# ADS_1.net
KiCad netlist of a schematic drawn in Altium Designer
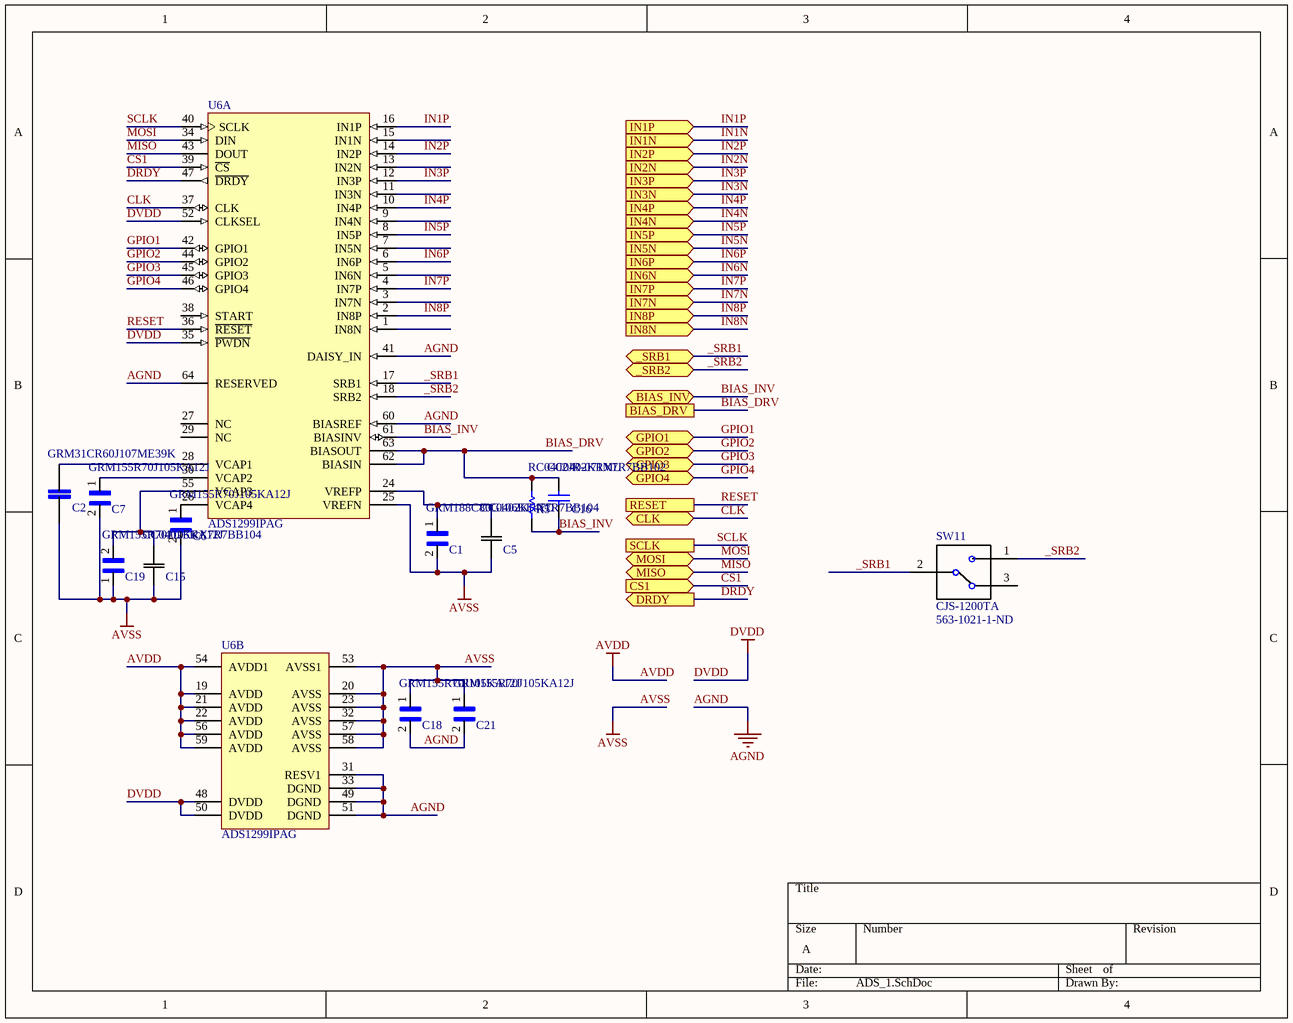
[diagram p0: ADS_1.SchDoc]

(export (version "E")
  (design (tool "Eeschema 10.0.6"))
  (components
    (comp (ref "C1")
      (value "GRM188C80G106KE47D")
      (footprint "*CAPC1608X90N")
      (description "CAP CER 10UF 4V X6S 0603")
      (fields (field (name "TOLERANCE") "10%"))
      (libsource (lib "EE_smallOB_BW_v1.0") (part "GRM188C80G106KE47D"))
    )
    (comp (ref "C2")
      (value "GRM31CR60J107ME39K")
      (footprint "*CAPC3216X190")
      (description "MURATA - GRM31CR60J107ME39K - COND, 100µF, 6.3V, 20%, X5R, 1206")
      (fields (field (name "TOLERANCE") "20%") (field (name "VOLTAGE") "6.3V"))
      (libsource (lib "EE_smallOB_BW_v1.0") (part "GRM31CR60J107ME39K"))
    )
    (comp (ref "C5")
      (value "CC0402KRX7R7BB104")
      (footprint "YAG_CC0402")
      (description "CAP CER 0.1UF 16V X7R 0402")
      (fields (field (name "TOLERANCE") "10%") (field (name "VOLTAGE") "16V"))
      (libsource (lib "EE_smallOB_BW_v1.0") (part "CC0402KRX7R7BB104"))
    )
    (comp (ref "C6")
      (value "GRM155R70J105KA12J")
      (footprint "*CAPC1005X55N")
      (description "CAP CER 1UF 6.3V X7R 0402")
      (fields (field (name "TOLERANCE") "10%"))
      (libsource (lib "EE_smallOB_BW_v1.0") (part "GRM155R70J105KA12J"))
    )
    (comp (ref "C7")
      (value "GRM155R70J105KA12J")
      (footprint "*CAPC1005X55N")
      (description "CAP CER 1UF 6.3V X7R 0402")
      (fields (field (name "TOLERANCE") "10%"))
      (libsource (lib "EE_smallOB_BW_v1.0") (part "GRM155R70J105KA12J"))
    )
    (comp (ref "C15")
      (value "CC0402KRX7R7BB104")
      (footprint "YAG_CC0402")
      (description "CAP CER 0.1UF 16V X7R 0402")
      (fields (field (name "TOLERANCE") "10%") (field (name "VOLTAGE") "16V"))
      (libsource (lib "EE_smallOB_BW_v1.0") (part "CC0402KRX7R7BB104"))
    )
    (comp (ref "C16")
      (value "CC0402KRX7R7BB102")
      (footprint "CAPC1005X55X23NL05T08")
      (description "CAP CER 1000PF 16V X7R 0402")
      (fields (field (name "TOLERANCE") "10%"))
      (libsource (lib "EE_smallOB_BW_v1.0") (part "CC0402KRX7R7BB102"))
    )
    (comp (ref "C18")
      (value "GRM155R70J105KA12J")
      (footprint "*CAPC1005X55N")
      (description "CAP CER 1UF 6.3V X7R 0402")
      (fields (field (name "TOLERANCE") "10%"))
      (libsource (lib "EE_smallOB_BW_v1.0") (part "GRM155R70J105KA12J"))
    )
    (comp (ref "C19")
      (value "GRM155R70J105KA12J")
      (footprint "*CAPC1005X55N")
      (description "CAP CER 1UF 6.3V X7R 0402")
      (fields (field (name "TOLERANCE") "10%"))
      (libsource (lib "EE_smallOB_BW_v1.0") (part "GRM155R70J105KA12J"))
    )
    (comp (ref "C21")
      (value "GRM155R70J105KA12J")
      (footprint "*CAPC1005X55N")
      (description "CAP CER 1UF 6.3V X7R 0402")
      (fields (field (name "TOLERANCE") "10%"))
      (libsource (lib "EE_smallOB_BW_v1.0") (part "GRM155R70J105KA12J"))
    )
    (comp (ref "R5")
      (value "RC0402JR-071ML")
      (footprint "RESC1005X40X25NL05T10")
      (description "RES SMD 1M OHM 5% 1/16W 0402")
      (fields (field (name "TOLERANCE") "5%"))
      (libsource (lib "EE_smallOB_BW_v1.0") (part "RC0402JR-071ML"))
    )
    (comp (ref "SW11")
      (value "CJS-1200TA")
      (footprint "*SW_CJS-1200TA")
      (description "SWITCH SLIDE SPDT 100MA 6V")
      (fields (field (name "SUPPLIER PART NUMBER 1") "563-1021-1-ND"))
      (libsource (lib "EE_smallOB_BW_v1.0") (part "CJS-1200TA"))
    )
    (comp (ref "U6")
      (value "ADS1299IPAG")
      (footprint "PAG0064A_N")
      (description "IC AFE 24BIT 16KSPS LN 64TQFP")
      (libsource (lib "EE_smallOB_BW_v1.0") (part "ADS1299IPAG"))
    )
  )
  (nets
    (net (code "1") (name "/BIAS_DRV") (class "Default")
      (node (ref "C16") (pin "1") (pinfunction "1_1") (pintype "passive"))
      (node (ref "R5") (pin "1") (pinfunction "1_1") (pintype "passive"))
      (node (ref "U6") (pin "62") (pinfunction "BIASIN_62") (pintype "passive"))
      (node (ref "U6") (pin "63") (pinfunction "BIASOUT_63") (pintype "passive"))
    )
    (net (code "2") (name "/BIAS_INV") (class "Default")
      (node (ref "C16") (pin "2") (pinfunction "2_2") (pintype "passive"))
      (node (ref "R5") (pin "2") (pinfunction "2_2") (pintype "passive"))
      (node (ref "U6") (pin "61") (pinfunction "BIASINV_61") (pintype "bidirectional"))
    )
    (net (code "3") (name "/CLK") (class "Default")
      (node (ref "U6") (pin "37") (pinfunction "CLK_37") (pintype "bidirectional"))
    )
    (net (code "4") (name "/CS1") (class "Default")
      (node (ref "U6") (pin "39") (pinfunction "~{CS}_39") (pintype "input"))
    )
    (net (code "5") (name "/DRDY") (class "Default")
      (node (ref "U6") (pin "47") (pinfunction "~{DRDY}_47") (pintype "output"))
    )
    (net (code "6") (name "/GPIO1") (class "Default")
      (node (ref "U6") (pin "42") (pinfunction "GPIO1_42") (pintype "bidirectional"))
    )
    (net (code "7") (name "/GPIO2") (class "Default")
      (node (ref "U6") (pin "44") (pinfunction "GPIO2_44") (pintype "bidirectional"))
    )
    (net (code "8") (name "/GPIO3") (class "Default")
      (node (ref "U6") (pin "45") (pinfunction "GPIO3_45") (pintype "bidirectional"))
    )
    (net (code "9") (name "/GPIO4") (class "Default")
      (node (ref "U6") (pin "46") (pinfunction "GPIO4_46") (pintype "bidirectional"))
    )
    (net (code "11") (name "/IN1P") (class "Default")
      (node (ref "U6") (pin "16") (pinfunction "IN1P_16") (pintype "input"))
    )
    (net (code "13") (name "/IN2P") (class "Default")
      (node (ref "U6") (pin "14") (pinfunction "IN2P_14") (pintype "input"))
    )
    (net (code "15") (name "/IN3P") (class "Default")
      (node (ref "U6") (pin "12") (pinfunction "IN3P_12") (pintype "input"))
    )
    (net (code "17") (name "/IN4P") (class "Default")
      (node (ref "U6") (pin "10") (pinfunction "IN4P_10") (pintype "input"))
    )
    (net (code "19") (name "/IN5P") (class "Default")
      (node (ref "U6") (pin "8") (pinfunction "IN5P_8") (pintype "input"))
    )
    (net (code "21") (name "/IN6P") (class "Default")
      (node (ref "U6") (pin "6") (pinfunction "IN6P_6") (pintype "input"))
    )
    (net (code "23") (name "/IN7P") (class "Default")
      (node (ref "U6") (pin "4") (pinfunction "IN7P_4") (pintype "input"))
    )
    (net (code "25") (name "/IN8P") (class "Default")
      (node (ref "U6") (pin "2") (pinfunction "IN8P_2") (pintype "input"))
    )
    (net (code "26") (name "/MISO") (class "Default")
      (node (ref "U6") (pin "43") (pinfunction "DOUT_43") (pintype "tri_state"))
    )
    (net (code "27") (name "/MOSI") (class "Default")
      (node (ref "U6") (pin "34") (pinfunction "DIN_34") (pintype "input"))
    )
    (net (code "28") (name "/RESET") (class "Default")
      (node (ref "U6") (pin "36") (pinfunction "~{RESET}_36") (pintype "input"))
    )
    (net (code "29") (name "/SCLK") (class "Default")
      (node (ref "U6") (pin "40") (pinfunction "SCLK_40") (pintype "input"))
    )
    (net (code "30") (name "/_SRB1") (class "Default")
      (node (ref "SW11") (pin "2") (pinfunction "2_2") (pintype "passive"))
      (node (ref "U6") (pin "17") (pinfunction "SRB1_17") (pintype "input"))
    )
    (net (code "31") (name "/_SRB2") (class "Default")
      (node (ref "SW11") (pin "1") (pinfunction "1_1") (pintype "passive"))
      (node (ref "U6") (pin "18") (pinfunction "SRB2_18") (pintype "input"))
    )
    (net (code "32") (name "AGND") (class "Default")
      (node (ref "C18") (pin "2") (pinfunction "2_2") (pintype "passive"))
      (node (ref "C21") (pin "2") (pinfunction "2_2") (pintype "passive"))
      (node (ref "U6") (pin "31") (pinfunction "RESV1_31") (pintype "power_in"))
      (node (ref "U6") (pin "33") (pinfunction "DGND_33") (pintype "power_in"))
      (node (ref "U6") (pin "41") (pinfunction "DAISY_IN_41") (pintype "input"))
      (node (ref "U6") (pin "49") (pinfunction "DGND_49") (pintype "power_in"))
      (node (ref "U6") (pin "51") (pinfunction "DGND_51") (pintype "power_in"))
      (node (ref "U6") (pin "60") (pinfunction "BIASREF_60") (pintype "input"))
      (node (ref "U6") (pin "64") (pinfunction "RESERVED_64") (pintype "passive"))
    )
    (net (code "33") (name "AVDD") (class "Default")
      (node (ref "U6") (pin "19") (pinfunction "AVDD_19") (pintype "power_in"))
      (node (ref "U6") (pin "21") (pinfunction "AVDD_21") (pintype "power_in"))
      (node (ref "U6") (pin "22") (pinfunction "AVDD_22") (pintype "power_in"))
      (node (ref "U6") (pin "54") (pinfunction "AVDD1_54") (pintype "power_in"))
      (node (ref "U6") (pin "56") (pinfunction "AVDD_56") (pintype "power_in"))
      (node (ref "U6") (pin "59") (pinfunction "AVDD_59") (pintype "power_in"))
    )
    (net (code "34") (name "AVSS") (class "Default")
      (node (ref "C1") (pin "2") (pinfunction "2_2") (pintype "passive"))
      (node (ref "C15") (pin "1") (pinfunction "1_1") (pintype "passive"))
      (node (ref "C18") (pin "1") (pinfunction "1_1") (pintype "passive"))
      (node (ref "C19") (pin "1") (pinfunction "1_1") (pintype "passive"))
      (node (ref "C2") (pin "2") (pinfunction "2_2") (pintype "passive"))
      (node (ref "C21") (pin "1") (pinfunction "1_1") (pintype "passive"))
      (node (ref "C5") (pin "2") (pinfunction "2_2") (pintype "passive"))
      (node (ref "C6") (pin "2") (pinfunction "2_2") (pintype "passive"))
      (node (ref "C7") (pin "2") (pinfunction "2_2") (pintype "passive"))
      (node (ref "U6") (pin "20") (pinfunction "AVSS_20") (pintype "power_in"))
      (node (ref "U6") (pin "23") (pinfunction "AVSS_23") (pintype "power_in"))
      (node (ref "U6") (pin "25") (pinfunction "VREFN_25") (pintype "passive"))
      (node (ref "U6") (pin "32") (pinfunction "AVSS_32") (pintype "power_in"))
      (node (ref "U6") (pin "53") (pinfunction "AVSS1_53") (pintype "power_in"))
      (node (ref "U6") (pin "57") (pinfunction "AVSS_57") (pintype "power_in"))
      (node (ref "U6") (pin "58") (pinfunction "AVSS_58") (pintype "power_in"))
    )
    (net (code "35") (name "DVDD") (class "Default")
      (node (ref "U6") (pin "35") (pinfunction "~{PWDN}_35") (pintype "input"))
      (node (ref "U6") (pin "48") (pinfunction "DVDD_48") (pintype "power_in"))
      (node (ref "U6") (pin "50") (pinfunction "DVDD_50") (pintype "power_in"))
      (node (ref "U6") (pin "52") (pinfunction "CLKSEL_52") (pintype "input"))
    )
    (net (code "36") (name "Net-(U6A-VCAP1)") (class "Default")
      (node (ref "C2") (pin "1") (pinfunction "1_1") (pintype "passive"))
      (node (ref "U6") (pin "28") (pinfunction "VCAP1_28") (pintype "passive"))
    )
    (net (code "37") (name "Net-(U6A-VCAP2)") (class "Default")
      (node (ref "C7") (pin "1") (pinfunction "1_1") (pintype "passive"))
      (node (ref "U6") (pin "30") (pinfunction "VCAP2_30") (pintype "passive"))
    )
    (net (code "38") (name "Net-(U6A-VCAP3)") (class "Default")
      (node (ref "C15") (pin "2") (pinfunction "2_2") (pintype "passive"))
      (node (ref "C19") (pin "2") (pinfunction "2_2") (pintype "passive"))
      (node (ref "U6") (pin "55") (pinfunction "VCAP3_55") (pintype "passive"))
    )
    (net (code "39") (name "Net-(U6A-VCAP4)") (class "Default")
      (node (ref "C6") (pin "1") (pinfunction "1_1") (pintype "passive"))
      (node (ref "U6") (pin "26") (pinfunction "VCAP4_26") (pintype "passive"))
    )
    (net (code "40") (name "Net-(U6A-VREFP)") (class "Default")
      (node (ref "C1") (pin "1") (pinfunction "1_1") (pintype "passive"))
      (node (ref "C5") (pin "1") (pinfunction "1_1") (pintype "passive"))
      (node (ref "U6") (pin "24") (pinfunction "VREFP_24") (pintype "passive"))
    )
    (net (code "41") (name "unconnected-(SW11-Pad3)") (class "Default")
      (node (ref "SW11") (pin "3") (pinfunction "3_3") (pintype "passive"))
    )
    (net (code "42") (name "unconnected-(U6A-IN1N-Pad15)") (class "Default")
      (node (ref "U6") (pin "15") (pinfunction "IN1N_15") (pintype "input"))
    )
    (net (code "43") (name "unconnected-(U6A-IN2N-Pad13)") (class "Default")
      (node (ref "U6") (pin "13") (pinfunction "IN2N_13") (pintype "input"))
    )
    (net (code "44") (name "unconnected-(U6A-IN3N-Pad11)") (class "Default")
      (node (ref "U6") (pin "11") (pinfunction "IN3N_11") (pintype "input"))
    )
    (net (code "45") (name "unconnected-(U6A-IN4N-Pad9)") (class "Default")
      (node (ref "U6") (pin "9") (pinfunction "IN4N_9") (pintype "input"))
    )
    (net (code "46") (name "unconnected-(U6A-IN5N-Pad7)") (class "Default")
      (node (ref "U6") (pin "7") (pinfunction "IN5N_7") (pintype "input"))
    )
    (net (code "47") (name "unconnected-(U6A-IN6N-Pad5)") (class "Default")
      (node (ref "U6") (pin "5") (pinfunction "IN6N_5") (pintype "input"))
    )
    (net (code "48") (name "unconnected-(U6A-IN7N-Pad3)") (class "Default")
      (node (ref "U6") (pin "3") (pinfunction "IN7N_3") (pintype "input"))
    )
    (net (code "49") (name "unconnected-(U6A-IN8N-Pad1)") (class "Default")
      (node (ref "U6") (pin "1") (pinfunction "IN8N_1") (pintype "input"))
    )
    (net (code "50") (name "unconnected-(U6A-NC-Pad27)") (class "Default")
      (node (ref "U6") (pin "27") (pinfunction "NC_27") (pintype "passive"))
    )
    (net (code "51") (name "unconnected-(U6A-NC-Pad29)") (class "Default")
      (node (ref "U6") (pin "29") (pinfunction "NC_29") (pintype "passive"))
    )
    (net (code "52") (name "unconnected-(U6A-START-Pad38)") (class "Default")
      (node (ref "U6") (pin "38") (pinfunction "START_38") (pintype "input"))
    )
  )
)
